# SNES_RGBAmp_wCSYNC_SVid.net
KiCad netlist of a schematic drawn in EAGLE
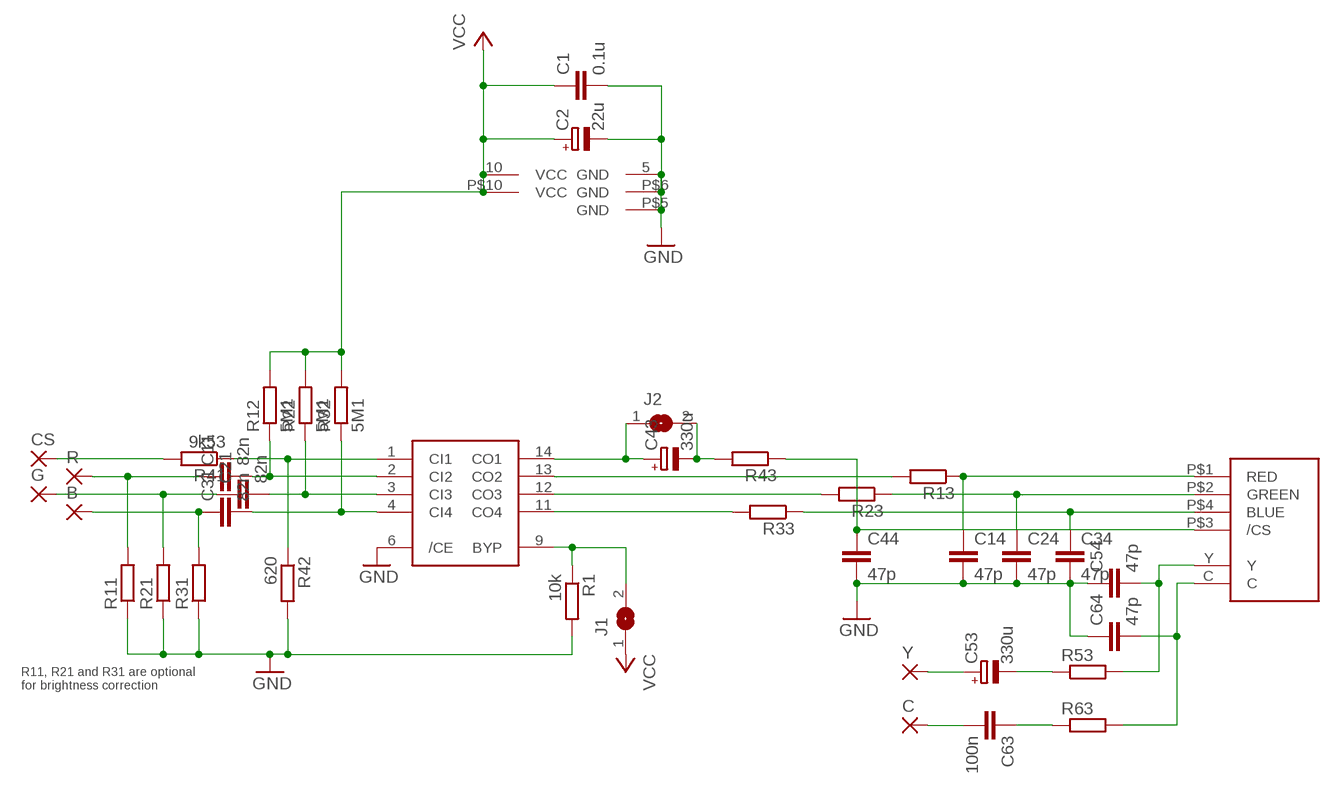
[diagram p0: schematic, sheet 1]

(export (version "E")
  (design (tool "Eeschema 10.0.6"))
  (components
    (comp (ref "B")
      (value "SMD2")
      (footprint "eagle-import:SMD1,27-2,54")
      (libsource (lib "eagle-import") (part "SMD2"))
    )
    (comp (ref "C")
      (value "SMD2")
      (footprint "eagle-import:SMD1,27-2,54")
      (libsource (lib "eagle-import") (part "SMD2"))
    )
    (comp (ref "C1")
      (value "0.1u")
      (footprint "eagle-import:C0603K")
      (libsource (lib "eagle-import") (part "C-EUC0603K"))
    )
    (comp (ref "C2")
      (value "22u")
      (footprint "eagle-import:SMC_B")
      (libsource (lib "eagle-import") (part "CPOL-EUSMCB"))
    )
    (comp (ref "C11")
      (value "82n")
      (footprint "eagle-import:C0603K")
      (libsource (lib "eagle-import") (part "C-EUC0603K"))
    )
    (comp (ref "C14")
      (value "47p")
      (footprint "eagle-import:C0603K")
      (libsource (lib "eagle-import") (part "C-EUC0603K"))
    )
    (comp (ref "C21")
      (value "82n")
      (footprint "eagle-import:C0603K")
      (libsource (lib "eagle-import") (part "C-EUC0603K"))
    )
    (comp (ref "C24")
      (value "47p")
      (footprint "eagle-import:C0603K")
      (libsource (lib "eagle-import") (part "C-EUC0603K"))
    )
    (comp (ref "C31")
      (value "82n")
      (footprint "eagle-import:C0603K")
      (libsource (lib "eagle-import") (part "C-EUC0603K"))
    )
    (comp (ref "C34")
      (value "47p")
      (footprint "eagle-import:C0603K")
      (libsource (lib "eagle-import") (part "C-EUC0603K"))
    )
    (comp (ref "C43")
      (value "330u")
      (footprint "eagle-import:SMC_D")
      (libsource (lib "eagle-import") (part "CPOL-EUSMCD"))
    )
    (comp (ref "C44")
      (value "47p")
      (footprint "eagle-import:C0603K")
      (libsource (lib "eagle-import") (part "C-EUC0603K"))
    )
    (comp (ref "C53")
      (value "330u")
      (footprint "eagle-import:SMC_D")
      (libsource (lib "eagle-import") (part "CPOL-EUSMCD"))
    )
    (comp (ref "C54")
      (value "47p")
      (footprint "eagle-import:C0603K")
      (libsource (lib "eagle-import") (part "C-EUC0603K"))
    )
    (comp (ref "C63")
      (value "100n")
      (footprint "eagle-import:C0603K")
      (libsource (lib "eagle-import") (part "C-EUC0603K"))
    )
    (comp (ref "C64")
      (value "47p")
      (footprint "eagle-import:C0603K")
      (libsource (lib "eagle-import") (part "C-EUC0603K"))
    )
    (comp (ref "CS")
      (value "SMD2")
      (footprint "eagle-import:SMD1,27-2,54")
      (libsource (lib "eagle-import") (part "SMD2"))
    )
    (comp (ref "G")
      (value "SMD2")
      (footprint "eagle-import:SMD1,27-2,54")
      (libsource (lib "eagle-import") (part "SMD2"))
    )
    (comp (ref "J1") (value "SJ") (footprint "eagle-import:SJ") (libsource (lib "eagle-import") (part "SJ")))
    (comp (ref "J2") (value "SJ") (footprint "eagle-import:SJ") (libsource (lib "eagle-import") (part "SJ")))
    (comp (ref "R")
      (value "SMD2")
      (footprint "eagle-import:SMD1,27-2,54")
      (libsource (lib "eagle-import") (part "SMD2"))
    )
    (comp (ref "R1")
      (value "10k")
      (footprint "eagle-import:R0603")
      (libsource (lib "eagle-import") (part "R-EU_R0603"))
    )
    (comp (ref "R11")
      (value "R-EU_R0603")
      (footprint "eagle-import:R0603")
      (libsource (lib "eagle-import") (part "R-EU_R0603"))
    )
    (comp (ref "R12")
      (value "5M1")
      (footprint "eagle-import:R0603")
      (libsource (lib "eagle-import") (part "R-EU_R0603"))
    )
    (comp (ref "R13")
      (value "R-EU_R0603")
      (footprint "eagle-import:R0603")
      (libsource (lib "eagle-import") (part "R-EU_R0603"))
    )
    (comp (ref "R21")
      (value "R-EU_R0603")
      (footprint "eagle-import:R0603")
      (libsource (lib "eagle-import") (part "R-EU_R0603"))
    )
    (comp (ref "R22")
      (value "5M1")
      (footprint "eagle-import:R0603")
      (libsource (lib "eagle-import") (part "R-EU_R0603"))
    )
    (comp (ref "R23")
      (value "R-EU_R0603")
      (footprint "eagle-import:R0603")
      (libsource (lib "eagle-import") (part "R-EU_R0603"))
    )
    (comp (ref "R31")
      (value "R-EU_R0603")
      (footprint "eagle-import:R0603")
      (libsource (lib "eagle-import") (part "R-EU_R0603"))
    )
    (comp (ref "R32")
      (value "5M1")
      (footprint "eagle-import:R0603")
      (libsource (lib "eagle-import") (part "R-EU_R0603"))
    )
    (comp (ref "R33")
      (value "R-EU_R0603")
      (footprint "eagle-import:R0603")
      (libsource (lib "eagle-import") (part "R-EU_R0603"))
    )
    (comp (ref "R41")
      (value "9k53")
      (footprint "eagle-import:R0603")
      (libsource (lib "eagle-import") (part "R-EU_R0603"))
    )
    (comp (ref "R42")
      (value "620")
      (footprint "eagle-import:R0603")
      (libsource (lib "eagle-import") (part "R-EU_R0603"))
    )
    (comp (ref "R43")
      (value "R-EU_R0603")
      (footprint "eagle-import:R0603")
      (libsource (lib "eagle-import") (part "R-EU_R0603"))
    )
    (comp (ref "R53")
      (value "R-EU_R0603")
      (footprint "eagle-import:R0603")
      (libsource (lib "eagle-import") (part "R-EU_R0603"))
    )
    (comp (ref "R63")
      (value "R-EU_R0603")
      (footprint "eagle-import:R0603")
      (libsource (lib "eagle-import") (part "R-EU_R0603"))
    )
    (comp (ref "U$1")
      (value "SNES_MULTIAV_RGBSYC")
      (footprint "eagle-import:SNES_MULTIAV_RGBSYC")
      (libsource (lib "eagle-import") (part "SNES_MULTIAV_RGBSYC"))
    )
    (comp (ref "U1")
      (value "THS7374")
      (footprint "eagle-import:THS7374")
      (libsource (lib "eagle-import") (part "THS7374"))
    )
    (comp (ref "Y")
      (value "SMD2")
      (footprint "eagle-import:SMD1,27-2,54")
      (libsource (lib "eagle-import") (part "SMD2"))
    )
  )
  (nets
    (net (code "1") (name "GND") (class "Default")
      (node (ref "C1") (pin "2") (pinfunction "2_2") (pintype "passive"))
      (node (ref "C14") (pin "2") (pinfunction "2_2") (pintype "passive"))
      (node (ref "C2") (pin "-") (pinfunction "-_-") (pintype "passive"))
      (node (ref "C24") (pin "2") (pinfunction "2_2") (pintype "passive"))
      (node (ref "C34") (pin "2") (pinfunction "2_2") (pintype "passive"))
      (node (ref "C44") (pin "2") (pinfunction "2_2") (pintype "passive"))
      (node (ref "C54") (pin "1") (pinfunction "1_1") (pintype "passive"))
      (node (ref "C64") (pin "1") (pinfunction "1_1") (pintype "passive"))
      (node (ref "R1") (pin "2") (pinfunction "2_2") (pintype "passive"))
      (node (ref "R11") (pin "1") (pinfunction "1_1") (pintype "passive"))
      (node (ref "R21") (pin "1") (pinfunction "1_1") (pintype "passive"))
      (node (ref "R31") (pin "1") (pinfunction "1_1") (pintype "passive"))
      (node (ref "R42") (pin "2") (pinfunction "2_2") (pintype "passive"))
      (node (ref "U$1") (pin "P$5") (pinfunction "GND_P$5") (pintype "bidirectional"))
      (node (ref "U$1") (pin "P$6") (pinfunction "GND_P$6") (pintype "bidirectional"))
      (node (ref "U1") (pin "5") (pinfunction "GND_5") (pintype "bidirectional"))
      (node (ref "U1") (pin "6") (pinfunction "/CE_6") (pintype "bidirectional"))
    )
    (net (code "2") (name "Net-(B-P)") (class "Default")
      (node (ref "B") (pin "1") (pinfunction "P_1") (pintype "passive"))
      (node (ref "C31") (pin "1") (pinfunction "1_1") (pintype "passive"))
      (node (ref "R31") (pin "2") (pinfunction "2_2") (pintype "passive"))
    )
    (net (code "3") (name "Net-(C-P)") (class "Default")
      (node (ref "C") (pin "1") (pinfunction "P_1") (pintype "passive"))
      (node (ref "C63") (pin "2") (pinfunction "2_2") (pintype "passive"))
    )
    (net (code "4") (name "Net-(C43-Pad-)") (class "Default")
      (node (ref "C43") (pin "-") (pinfunction "-_-") (pintype "passive"))
      (node (ref "J2") (pin "2") (pinfunction "2_2") (pintype "passive"))
      (node (ref "R43") (pin "2") (pinfunction "2_2") (pintype "passive"))
    )
    (net (code "5") (name "Net-(C53-Pad-)") (class "Default")
      (node (ref "C53") (pin "-") (pinfunction "-_-") (pintype "passive"))
      (node (ref "R53") (pin "1") (pinfunction "1_1") (pintype "passive"))
    )
    (net (code "6") (name "Net-(C54-Pad2)") (class "Default")
      (node (ref "C54") (pin "2") (pinfunction "2_2") (pintype "passive"))
      (node (ref "R53") (pin "2") (pinfunction "2_2") (pintype "passive"))
      (node (ref "U$1") (pin "Y") (pinfunction "Y_Y") (pintype "bidirectional"))
    )
    (net (code "7") (name "Net-(C63-Pad1)") (class "Default")
      (node (ref "C63") (pin "1") (pinfunction "1_1") (pintype "passive"))
      (node (ref "R63") (pin "1") (pinfunction "1_1") (pintype "passive"))
    )
    (net (code "8") (name "Net-(C64-Pad2)") (class "Default")
      (node (ref "C64") (pin "2") (pinfunction "2_2") (pintype "passive"))
      (node (ref "R63") (pin "2") (pinfunction "2_2") (pintype "passive"))
      (node (ref "U$1") (pin "C") (pinfunction "C_C") (pintype "bidirectional"))
    )
    (net (code "9") (name "Net-(CS-P)") (class "Default")
      (node (ref "CS") (pin "1") (pinfunction "P_1") (pintype "passive"))
      (node (ref "R41") (pin "2") (pinfunction "2_2") (pintype "passive"))
    )
    (net (code "10") (name "Net-(G-P)") (class "Default")
      (node (ref "C21") (pin "1") (pinfunction "1_1") (pintype "passive"))
      (node (ref "G") (pin "1") (pinfunction "P_1") (pintype "passive"))
      (node (ref "R21") (pin "2") (pinfunction "2_2") (pintype "passive"))
    )
    (net (code "11") (name "Net-(R-P)") (class "Default")
      (node (ref "C11") (pin "1") (pinfunction "1_1") (pintype "passive"))
      (node (ref "R") (pin "1") (pinfunction "P_1") (pintype "passive"))
      (node (ref "R11") (pin "2") (pinfunction "2_2") (pintype "passive"))
    )
    (net (code "12") (name "Net-(U$1A-BLUE)") (class "Default")
      (node (ref "C34") (pin "1") (pinfunction "1_1") (pintype "passive"))
      (node (ref "R33") (pin "1") (pinfunction "1_1") (pintype "passive"))
      (node (ref "U$1") (pin "P$4") (pinfunction "BLUE_P$4") (pintype "bidirectional"))
    )
    (net (code "13") (name "Net-(U$1A-GREEN)") (class "Default")
      (node (ref "C24") (pin "1") (pinfunction "1_1") (pintype "passive"))
      (node (ref "R23") (pin "1") (pinfunction "1_1") (pintype "passive"))
      (node (ref "U$1") (pin "P$2") (pinfunction "GREEN_P$2") (pintype "bidirectional"))
    )
    (net (code "14") (name "Net-(U$1A-RED)") (class "Default")
      (node (ref "C14") (pin "1") (pinfunction "1_1") (pintype "passive"))
      (node (ref "R13") (pin "1") (pinfunction "1_1") (pintype "passive"))
      (node (ref "U$1") (pin "P$1") (pinfunction "RED_P$1") (pintype "bidirectional"))
    )
    (net (code "15") (name "Net-(U$1A-{slash}CS)") (class "Default")
      (node (ref "C44") (pin "1") (pinfunction "1_1") (pintype "passive"))
      (node (ref "R43") (pin "1") (pinfunction "1_1") (pintype "passive"))
      (node (ref "U$1") (pin "P$3") (pinfunction "/CS_P$3") (pintype "bidirectional"))
    )
    (net (code "16") (name "Net-(U1A-BYP)") (class "Default")
      (node (ref "J1") (pin "2") (pinfunction "2_2") (pintype "passive"))
      (node (ref "R1") (pin "1") (pinfunction "1_1") (pintype "passive"))
      (node (ref "U1") (pin "9") (pinfunction "BYP_9") (pintype "bidirectional"))
    )
    (net (code "17") (name "Net-(U1A-CI1)") (class "Default")
      (node (ref "R41") (pin "1") (pinfunction "1_1") (pintype "passive"))
      (node (ref "R42") (pin "1") (pinfunction "1_1") (pintype "passive"))
      (node (ref "U1") (pin "1") (pinfunction "CI1_1") (pintype "bidirectional"))
    )
    (net (code "18") (name "Net-(U1A-CI2)") (class "Default")
      (node (ref "C11") (pin "2") (pinfunction "2_2") (pintype "passive"))
      (node (ref "R12") (pin "1") (pinfunction "1_1") (pintype "passive"))
      (node (ref "U1") (pin "2") (pinfunction "CI2_2") (pintype "bidirectional"))
    )
    (net (code "19") (name "Net-(U1A-CI3)") (class "Default")
      (node (ref "C21") (pin "2") (pinfunction "2_2") (pintype "passive"))
      (node (ref "R22") (pin "1") (pinfunction "1_1") (pintype "passive"))
      (node (ref "U1") (pin "3") (pinfunction "CI3_3") (pintype "bidirectional"))
    )
    (net (code "20") (name "Net-(U1A-CI4)") (class "Default")
      (node (ref "C31") (pin "2") (pinfunction "2_2") (pintype "passive"))
      (node (ref "R32") (pin "1") (pinfunction "1_1") (pintype "passive"))
      (node (ref "U1") (pin "4") (pinfunction "CI4_4") (pintype "bidirectional"))
    )
    (net (code "21") (name "Net-(U1A-CO1)") (class "Default")
      (node (ref "C43") (pin "+") (pinfunction "+_+") (pintype "passive"))
      (node (ref "J2") (pin "1") (pinfunction "1_1") (pintype "passive"))
      (node (ref "U1") (pin "14") (pinfunction "CO1_14") (pintype "bidirectional"))
    )
    (net (code "22") (name "Net-(U1A-CO2)") (class "Default")
      (node (ref "R13") (pin "2") (pinfunction "2_2") (pintype "passive"))
      (node (ref "U1") (pin "13") (pinfunction "CO2_13") (pintype "bidirectional"))
    )
    (net (code "23") (name "Net-(U1A-CO3)") (class "Default")
      (node (ref "R23") (pin "2") (pinfunction "2_2") (pintype "passive"))
      (node (ref "U1") (pin "12") (pinfunction "CO3_12") (pintype "bidirectional"))
    )
    (net (code "24") (name "Net-(U1A-CO4)") (class "Default")
      (node (ref "R33") (pin "2") (pinfunction "2_2") (pintype "passive"))
      (node (ref "U1") (pin "11") (pinfunction "CO4_11") (pintype "bidirectional"))
    )
    (net (code "25") (name "Net-(Y-P)") (class "Default")
      (node (ref "C53") (pin "+") (pinfunction "+_+") (pintype "passive"))
      (node (ref "Y") (pin "1") (pinfunction "P_1") (pintype "passive"))
    )
    (net (code "26") (name "VCC") (class "Default")
      (node (ref "C1") (pin "1") (pinfunction "1_1") (pintype "passive"))
      (node (ref "C2") (pin "+") (pinfunction "+_+") (pintype "passive"))
      (node (ref "J1") (pin "1") (pinfunction "1_1") (pintype "passive"))
      (node (ref "R12") (pin "2") (pinfunction "2_2") (pintype "passive"))
      (node (ref "R22") (pin "2") (pinfunction "2_2") (pintype "passive"))
      (node (ref "R32") (pin "2") (pinfunction "2_2") (pintype "passive"))
      (node (ref "U$1") (pin "P$10") (pinfunction "VCC_P$10") (pintype "bidirectional"))
      (node (ref "U1") (pin "10") (pinfunction "VCC_10") (pintype "bidirectional"))
    )
  )
)
